# LPFilter.net
KiCad netlist of a schematic drawn in Altium Designer
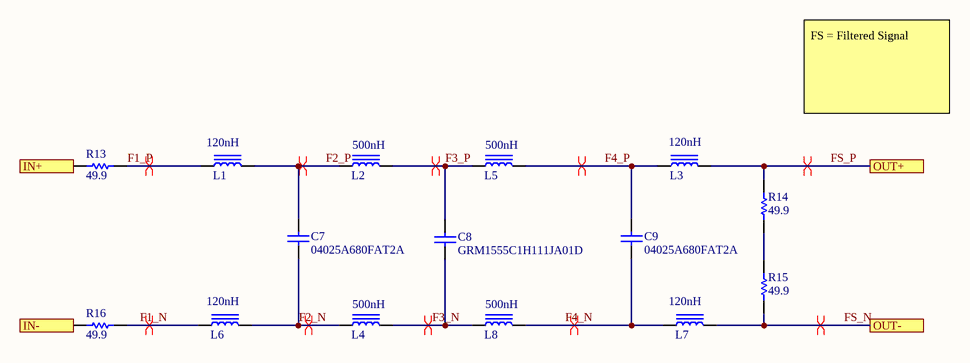
[diagram p0: LPFilter.SchDoc]

(export (version "E")
  (design (tool "Eeschema 10.0.6"))
  (components
    (comp (ref "C7")
      (value "04025A680FAT2A")
      (footprint "CAPC1005X56X25NL10T15")
      (fields (field (name "MANUFACTURER") "AVX Interconnect / Elco"))
      (libsource (lib "Altium Content Vault") (part "CAP"))
    )
    (comp (ref "C8")
      (value "GRM1555C1H111JA01D")
      (footprint "CAPC1005X55X25LL05T10")
      (fields (field (name "MANUFACTURER") "Murata"))
      (libsource (lib "Altium Content Vault") (part "CAP"))
    )
    (comp (ref "C9")
      (value "04025A680FAT2A")
      (footprint "CAPC1005X56X25NL10T15")
      (fields (field (name "MANUFACTURER") "AVX Interconnect / Elco"))
      (libsource (lib "Altium Content Vault") (part "CAP"))
    )
    (comp (ref "L1")
      (value "120nH")
      (footprint "FER 0805/2012")
      (description "FIXED IND 120NH 300MA 200 MOHM")
      (fields (field (name "PART NUMBER") "MLF2012DR12M") (field (name "MANUFACTURER") "TDK Corporation"))
      (libsource (lib "Celestial Library Database") (part "Inductor"))
    )
    (comp (ref "L2")
      (value "500nH")
      (footprint "CAP 1210/3225 - 1.2MM")
      (description "FIXED IND 500NH 3.8A 18 MOHM SMD")
      (fields
        (field (name "PART NUMBER") "74479899150")
        (field (name "MANUFACTURER") "Wurth Electronics Inc.")
      )
      (libsource (lib "Celestial Library Database") (part "Inductor"))
    )
    (comp (ref "L3")
      (value "120nH")
      (footprint "FER 0805/2012")
      (description "FIXED IND 120NH 300MA 200 MOHM")
      (fields (field (name "PART NUMBER") "MLF2012DR12M") (field (name "MANUFACTURER") "TDK Corporation"))
      (libsource (lib "Celestial Library Database") (part "Inductor"))
    )
    (comp (ref "L4")
      (value "500nH")
      (footprint "CAP 1210/3225 - 1.2MM")
      (description "FIXED IND 500NH 3.8A 18 MOHM SMD")
      (fields
        (field (name "PART NUMBER") "74479899150")
        (field (name "MANUFACTURER") "Wurth Electronics Inc.")
      )
      (libsource (lib "Celestial Library Database") (part "Inductor"))
    )
    (comp (ref "L5")
      (value "500nH")
      (footprint "CAP 1210/3225 - 1.2MM")
      (description "FIXED IND 500NH 3.8A 18 MOHM SMD")
      (fields
        (field (name "PART NUMBER") "74479899150")
        (field (name "MANUFACTURER") "Wurth Electronics Inc.")
      )
      (libsource (lib "Celestial Library Database") (part "Inductor"))
    )
    (comp (ref "L6")
      (value "120nH")
      (footprint "FER 0805/2012")
      (description "FIXED IND 120NH 300MA 200 MOHM")
      (fields (field (name "PART NUMBER") "MLF2012DR12M") (field (name "MANUFACTURER") "TDK Corporation"))
      (libsource (lib "Celestial Library Database") (part "Inductor"))
    )
    (comp (ref "L7")
      (value "120nH")
      (footprint "FER 0805/2012")
      (description "FIXED IND 120NH 300MA 200 MOHM")
      (fields (field (name "PART NUMBER") "MLF2012DR12M") (field (name "MANUFACTURER") "TDK Corporation"))
      (libsource (lib "Celestial Library Database") (part "Inductor"))
    )
    (comp (ref "L8")
      (value "500nH")
      (footprint "CAP 1210/3225 - 1.2MM")
      (description "FIXED IND 500NH 3.8A 18 MOHM SMD")
      (fields
        (field (name "PART NUMBER") "74479899150")
        (field (name "MANUFACTURER") "Wurth Electronics Inc.")
      )
      (libsource (lib "Celestial Library Database") (part "Inductor"))
    )
    (comp (ref "R13")
      (value "49.9")
      (footprint "RESC1005X40X25NL05T05")
      (fields (field (name "MANUFACTURER") "Panasonic") (field (name "PART NUMBER") "ERJ-2RKF49R9X"))
      (libsource (lib "Altium Content Vault") (part "RES"))
    )
    (comp (ref "R14")
      (value "49.9")
      (footprint "RESC1005X40X25NL05T05")
      (fields (field (name "MANUFACTURER") "Panasonic") (field (name "PART NUMBER") "ERJ-2RKF49R9X"))
      (libsource (lib "Altium Content Vault") (part "RES"))
    )
    (comp (ref "R15")
      (value "49.9")
      (footprint "RESC1005X40X25NL05T05")
      (fields (field (name "MANUFACTURER") "Panasonic") (field (name "PART NUMBER") "ERJ-2RKF49R9X"))
      (libsource (lib "Altium Content Vault") (part "RES"))
    )
    (comp (ref "R16")
      (value "49.9")
      (footprint "RESC1005X40X25NL05T05")
      (fields (field (name "MANUFACTURER") "Panasonic") (field (name "PART NUMBER") "ERJ-2RKF49R9X"))
      (libsource (lib "Altium Content Vault") (part "RES"))
    )
  )
  (nets
    (net (code "1") (name "/F1_N") (class "Default")
      (node (ref "L6") (pin "1") (pinfunction "1_1") (pintype "passive"))
      (node (ref "R16") (pin "2") (pinfunction "2_2") (pintype "passive"))
    )
    (net (code "2") (name "/F1_P") (class "Default")
      (node (ref "L1") (pin "1") (pinfunction "1_1") (pintype "passive"))
      (node (ref "R13") (pin "2") (pinfunction "2_2") (pintype "passive"))
    )
    (net (code "3") (name "/F2_N") (class "Default")
      (node (ref "C7") (pin "2") (pinfunction "2_2") (pintype "passive"))
      (node (ref "L4") (pin "1") (pinfunction "1_1") (pintype "passive"))
      (node (ref "L6") (pin "2") (pinfunction "2_2") (pintype "passive"))
    )
    (net (code "4") (name "/F2_P") (class "Default")
      (node (ref "C7") (pin "1") (pinfunction "1_1") (pintype "passive"))
      (node (ref "L1") (pin "2") (pinfunction "2_2") (pintype "passive"))
      (node (ref "L2") (pin "1") (pinfunction "1_1") (pintype "passive"))
    )
    (net (code "5") (name "/F3_N") (class "Default")
      (node (ref "C8") (pin "1") (pinfunction "1_1") (pintype "passive"))
      (node (ref "L4") (pin "2") (pinfunction "2_2") (pintype "passive"))
      (node (ref "L8") (pin "1") (pinfunction "1_1") (pintype "passive"))
    )
    (net (code "6") (name "/F3_P") (class "Default")
      (node (ref "C8") (pin "2") (pinfunction "2_2") (pintype "passive"))
      (node (ref "L2") (pin "2") (pinfunction "2_2") (pintype "passive"))
      (node (ref "L5") (pin "1") (pinfunction "1_1") (pintype "passive"))
    )
    (net (code "7") (name "/F4_N") (class "Default")
      (node (ref "C9") (pin "1") (pinfunction "1_1") (pintype "passive"))
      (node (ref "L7") (pin "1") (pinfunction "1_1") (pintype "passive"))
      (node (ref "L8") (pin "2") (pinfunction "2_2") (pintype "passive"))
    )
    (net (code "8") (name "/F4_P") (class "Default")
      (node (ref "C9") (pin "2") (pinfunction "2_2") (pintype "passive"))
      (node (ref "L3") (pin "1") (pinfunction "1_1") (pintype "passive"))
      (node (ref "L5") (pin "2") (pinfunction "2_2") (pintype "passive"))
    )
    (net (code "9") (name "/FS_N") (class "Default")
      (node (ref "L7") (pin "2") (pinfunction "2_2") (pintype "passive"))
      (node (ref "R15") (pin "1") (pinfunction "1_1") (pintype "passive"))
    )
    (net (code "10") (name "/FS_P") (class "Default")
      (node (ref "L3") (pin "2") (pinfunction "2_2") (pintype "passive"))
      (node (ref "R14") (pin "2") (pinfunction "2_2") (pintype "passive"))
    )
    (net (code "11") (name "/IN+") (class "Default")
      (node (ref "R13") (pin "1") (pinfunction "1_1") (pintype "passive"))
    )
    (net (code "12") (name "/IN-") (class "Default")
      (node (ref "R16") (pin "1") (pinfunction "1_1") (pintype "passive"))
    )
    (net (code "13") (name "Net-(R14-Pad1)") (class "Default")
      (node (ref "R14") (pin "1") (pinfunction "1_1") (pintype "passive"))
      (node (ref "R15") (pin "2") (pinfunction "2_2") (pintype "passive"))
    )
  )
)
